# power.net
KiCad netlist of a schematic drawn in Altium Designer
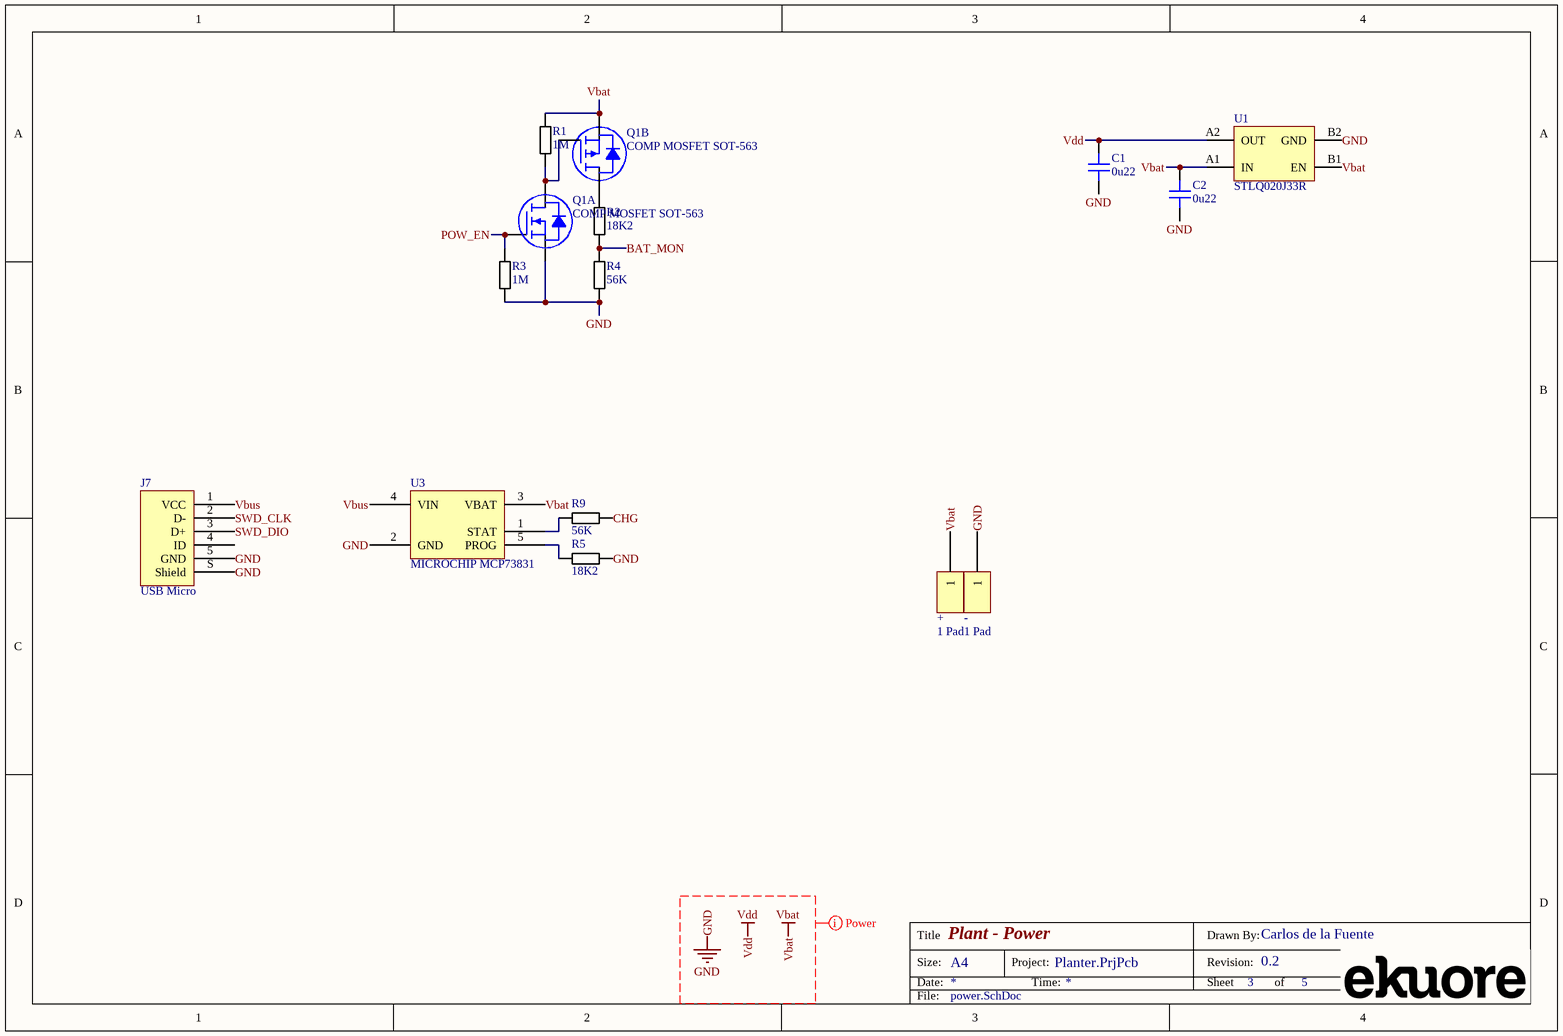
[diagram p0: power.SchDoc]

(export (version "E")
  (design (tool "Eeschema 10.0.6"))
  (components
    (comp (ref "+")
      (value "1 Pad")
      (footprint "HARWIN P70 - CONTACT")
      (description "CONTACT PAD P70 Pogo pin series")
      (fields (field (name "PART NUMBER") "P70 - Contact"))
      (libsource (lib "ekuore-library") (part "1 Pad"))
    )
    (comp (ref "-")
      (value "1 Pad")
      (footprint "HARWIN P70 - CONTACT")
      (description "CONTACT PAD P70 Pogo pin series")
      (fields (field (name "PART NUMBER") "P70 - Contact"))
      (libsource (lib "ekuore-library") (part "1 Pad"))
    )
    (comp (ref "C1")
      (value "0u22")
      (footprint "CAP 0201/0603")
      (description "CAP CER 0201 0.22uF 10V 10% X5R")
      (fields (field (name "PART NUMBER") "GRM033R61A224KE90D") (field (name "MANUFACTURER") "Murata"))
      (libsource (lib "ekuore-library") (part "Capacitor"))
    )
    (comp (ref "C2")
      (value "0u22")
      (footprint "CAP 0201/0603")
      (description "CAP CER 0201 0.22uF 10V 10% X5R")
      (fields (field (name "PART NUMBER") "GRM033R61A224KE90D") (field (name "MANUFACTURER") "Murata"))
      (libsource (lib "ekuore-library") (part "Capacitor"))
    )
    (comp (ref "J7")
      (value "USB Micro")
      (footprint "Amphenol 10118192")
      (description "CONN RCP USB2.0 MICRO B SMD R/A")
      (fields (field (name "PART NUMBER") "10118192-0001LF") (field (name "MANUFACTURER") "Amphenol FCI"))
      (libsource (lib "ekuore-library") (part "USB 2.0 Type B Micro"))
    )
    (comp (ref "Q1")
      (value "COMP MOSFET SOT-563")
      (footprint "ON SEMI SOT563")
      (description "MOSFET N/P-CH 20V 0.54A/-0.43A SOT563")
      (fields (field (name "PART NUMBER") "NTZD3155CT1G") (field (name "MANUFACTURER") "ON Semiconductor"))
      (libsource (lib "") (part "COMP MOSFET SOT-563_1"))
    )
    (comp (ref "R1")
      (value "1M")
      (footprint "RES 0402/1005")
      (description "RES 0402 1M 1%  63mW")
      (fields (field (name "PART NUMBER") "RC0402FR-071ML") (field (name "MANUFACTURER") "Yageo"))
      (libsource (lib "ekuore-library") (part "Resistor"))
    )
    (comp (ref "R2")
      (value "18K2")
      (footprint "RES 0402/1005")
      (description "RES 0402 18K2 1%  63mW")
      (fields (field (name "PART NUMBER") "RC0402FR-0718K2L") (field (name "MANUFACTURER") "Yageo"))
      (libsource (lib "ekuore-library") (part "Resistor"))
    )
    (comp (ref "R3")
      (value "1M")
      (footprint "RES 0402/1005")
      (description "RES 0402 1M 1%  63mW")
      (fields (field (name "PART NUMBER") "RC0402FR-071ML") (field (name "MANUFACTURER") "Yageo"))
      (libsource (lib "ekuore-library") (part "Resistor"))
    )
    (comp (ref "R4")
      (value "56K")
      (footprint "RES 0402/1005")
      (description "RES 0402 56K 1%  63mW")
      (fields (field (name "PART NUMBER") "RC0402FR-0756KL") (field (name "MANUFACTURER") "Yageo"))
      (libsource (lib "ekuore-library") (part "Resistor"))
    )
    (comp (ref "R5")
      (value "18K2")
      (footprint "RES 0402/1005")
      (description "RES 0402 18K2 1%  63mW")
      (fields (field (name "PART NUMBER") "RC0402FR-0718K2L") (field (name "MANUFACTURER") "Yageo"))
      (libsource (lib "ekuore-library") (part "Resistor"))
    )
    (comp (ref "R9")
      (value "56K")
      (footprint "RES 0402/1005")
      (description "RES 0402 56K 1%  63mW")
      (fields (field (name "PART NUMBER") "RC0402FR-0756KL") (field (name "MANUFACTURER") "Yageo"))
      (libsource (lib "ekuore-library") (part "Resistor"))
    )
    (comp (ref "U1")
      (value "STLQ020J33R")
      (footprint "ST flip-chip4")
      (description "IC REG LIN 3.3V 200MA 4FLIPCHIP")
      (fields (field (name "MANUFACTURER") "STMicroelectronics"))
      (libsource (lib "ekuore-library") (part "STLQ020_flip"))
    )
    (comp (ref "U3")
      (value "MICROCHIP MCP73831")
      (footprint "MICROCHIP SOT-23-5")
      (description "MICROCHIP - MCP73831T-2ACI/OT - LI-ION/LI-POLY CHA")
      (fields (field (name "PART NUMBER") "MCP73831T-2ACI/OT") (field (name "MANUFACTURER") "Microchip"))
      (libsource (lib "ekuore-library") (part "MICROCHIP MCP73831"))
    )
  )
  (nets
    (net (code "1") (name "/BAT_MON") (class "Default")
      (node (ref "R2") (pin "1") (pinfunction "1_1") (pintype "passive"))
      (node (ref "R4") (pin "2") (pinfunction "2_2") (pintype "passive"))
    )
    (net (code "2") (name "/CHG") (class "Default")
      (node (ref "R9") (pin "2") (pinfunction "2_2") (pintype "passive"))
    )
    (net (code "3") (name "/POW_EN") (class "Default")
      (node (ref "Q1") (pin "2") (pinfunction "G1_2") (pintype "passive"))
      (node (ref "R3") (pin "2") (pinfunction "2_2") (pintype "passive"))
    )
    (net (code "4") (name "/SWD_CLK") (class "Default")
      (node (ref "J7") (pin "2") (pinfunction "D-_2") (pintype "passive"))
    )
    (net (code "5") (name "/SWD_DIO") (class "Default")
      (node (ref "J7") (pin "3") (pinfunction "D+_3") (pintype "passive"))
    )
    (net (code "6") (name "/Vbus") (class "Default")
      (node (ref "J7") (pin "1") (pinfunction "VCC_1") (pintype "passive"))
      (node (ref "U3") (pin "4") (pinfunction "VIN_4") (pintype "passive"))
    )
    (net (code "7") (name "GND") (class "Default")
      (node (ref "-") (pin "1") (pinfunction "1_1") (pintype "passive"))
      (node (ref "C1") (pin "1") (pinfunction "1_1") (pintype "passive"))
      (node (ref "C2") (pin "1") (pinfunction "1_1") (pintype "passive"))
      (node (ref "J7") (pin "5") (pinfunction "GND_5") (pintype "passive"))
      (node (ref "J7") (pin "S") (pinfunction "Shield_S") (pintype "passive"))
      (node (ref "Q1") (pin "1") (pinfunction "S1_1") (pintype "passive"))
      (node (ref "R3") (pin "1") (pinfunction "1_1") (pintype "passive"))
      (node (ref "R4") (pin "1") (pinfunction "1_1") (pintype "passive"))
      (node (ref "R5") (pin "1") (pinfunction "1_1") (pintype "passive"))
      (node (ref "U1") (pin "B2") (pinfunction "GND_B2") (pintype "passive"))
      (node (ref "U3") (pin "2") (pinfunction "GND_2") (pintype "passive"))
    )
    (net (code "8") (name "Net-(Q1A-D1)") (class "Default")
      (node (ref "Q1") (pin "5") (pinfunction "G2_5") (pintype "passive"))
      (node (ref "Q1") (pin "6") (pinfunction "D1_6") (pintype "passive"))
      (node (ref "R1") (pin "1") (pinfunction "1_1") (pintype "passive"))
    )
    (net (code "9") (name "Net-(Q1B-D2)") (class "Default")
      (node (ref "Q1") (pin "3") (pinfunction "D2_3") (pintype "passive"))
      (node (ref "R2") (pin "2") (pinfunction "2_2") (pintype "passive"))
    )
    (net (code "10") (name "Net-(U3-PROG)") (class "Default")
      (node (ref "R5") (pin "2") (pinfunction "2_2") (pintype "passive"))
      (node (ref "U3") (pin "5") (pinfunction "PROG_5") (pintype "passive"))
    )
    (net (code "11") (name "Net-(U3-STAT)") (class "Default")
      (node (ref "R9") (pin "1") (pinfunction "1_1") (pintype "passive"))
      (node (ref "U3") (pin "1") (pinfunction "STAT_1") (pintype "passive"))
    )
    (net (code "12") (name "Vbat") (class "Default")
      (node (ref "+") (pin "1") (pinfunction "1_1") (pintype "passive"))
      (node (ref "C2") (pin "2") (pinfunction "2_2") (pintype "passive"))
      (node (ref "Q1") (pin "4") (pinfunction "S2_4") (pintype "passive"))
      (node (ref "R1") (pin "2") (pinfunction "2_2") (pintype "passive"))
      (node (ref "U1") (pin "A1") (pinfunction "IN_A1") (pintype "passive"))
      (node (ref "U1") (pin "B1") (pinfunction "EN_B1") (pintype "passive"))
      (node (ref "U3") (pin "3") (pinfunction "VBAT_3") (pintype "passive"))
    )
    (net (code "13") (name "Vdd") (class "Default")
      (node (ref "C1") (pin "2") (pinfunction "2_2") (pintype "passive"))
      (node (ref "U1") (pin "A2") (pinfunction "OUT_A2") (pintype "passive"))
    )
    (net (code "14") (name "unconnected-(J7-ID-Pad4)") (class "Default")
      (node (ref "J7") (pin "4") (pinfunction "ID_4") (pintype "passive"))
    )
  )
)
